# Earphone-6.net
KiCad netlist of a schematic drawn in Altium Designer
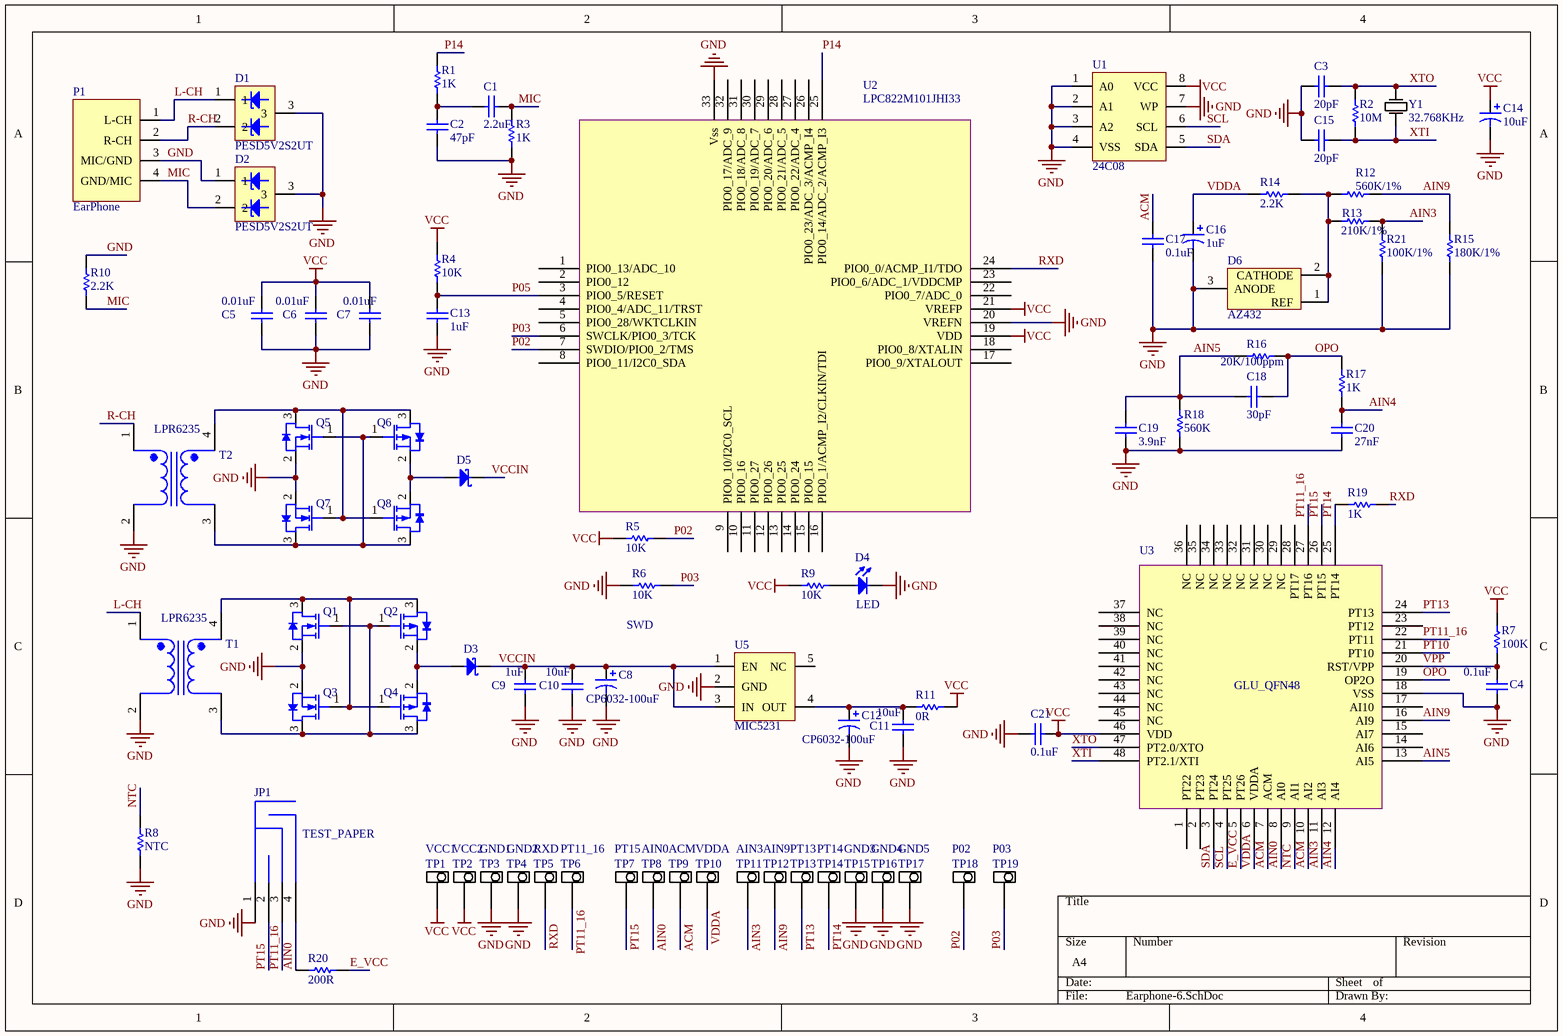
[diagram p0: Earphone-6.SchDoc]

(export (version "E")
  (design (tool "Eeschema 10.0.6"))
  (components
    (comp (ref "ACM") (value "TP9") (footprint "SIP1") (libsource (lib "Earphone") (part "TEST_PAD")))
    (comp (ref "AIN0") (value "TP8") (footprint "SIP1") (libsource (lib "Earphone") (part "TEST_PAD")))
    (comp (ref "AIN3") (value "TP11") (footprint "SIP1") (libsource (lib "Earphone") (part "TEST_PAD")))
    (comp (ref "AIN9") (value "TP12") (footprint "SIP1") (libsource (lib "Earphone") (part "TEST_PAD")))
    (comp (ref "C1") (value "2.2uF") (footprint "0402C") (libsource (lib "Schlib1") (part "CAP")))
    (comp (ref "C2") (value "47pF") (footprint "0402C") (libsource (lib "Schlib1") (part "CAP")))
    (comp (ref "C3") (value "20pF") (footprint "0402C") (libsource (lib "Earphone") (part "CAP")))
    (comp (ref "C4") (value "0.1uF") (footprint "0402C") (libsource (lib "Schlib1") (part "CAP")))
    (comp (ref "C5") (value "0.01uF") (footprint "0402C") (libsource (lib "Schlib1") (part "CAP")))
    (comp (ref "C6") (value "0.01uF") (footprint "0402C") (libsource (lib "Schlib1") (part "CAP")))
    (comp (ref "C7") (value "0.01uF") (footprint "0402C") (libsource (lib "Schlib1") (part "CAP")))
    (comp (ref "C8")
      (value "CP6032-100uF")
      (footprint "T3216-18[A]")
      (libsource (lib "Schlib1") (part "CAP POL2"))
    )
    (comp (ref "C9") (value "1uF") (footprint "0402C") (libsource (lib "Schlib1") (part "CAP")))
    (comp (ref "C10") (value "10uF") (footprint "0402C") (libsource (lib "Schlib1") (part "CAP")))
    (comp (ref "C11") (value "10uF") (footprint "0402C") (libsource (lib "Schlib1") (part "CAP")))
    (comp (ref "C12")
      (value "CP6032-100uF")
      (footprint "T3216-18[A]")
      (libsource (lib "Schlib1") (part "CAP POL2"))
    )
    (comp (ref "C13") (value "1uF") (footprint "0402C") (libsource (lib "Schlib1") (part "CAP")))
    (comp (ref "C14") (value "10uF") (footprint "0402C") (libsource (lib "Earphone") (part "CAP POL2")))
    (comp (ref "C15") (value "20pF") (footprint "0402C") (libsource (lib "Earphone") (part "CAP")))
    (comp (ref "C16") (value "1uF") (footprint "0402C") (libsource (lib "Earphone") (part "CAP POL2")))
    (comp (ref "C17") (value "0.1uF") (footprint "0402C") (libsource (lib "Earphone") (part "CAP")))
    (comp (ref "C18") (value "30pF") (footprint "0402C") (libsource (lib "Earphone") (part "CAP")))
    (comp (ref "C19") (value "3.9nF") (footprint "0402C") (libsource (lib "Earphone") (part "CAP")))
    (comp (ref "C20") (value "27nF") (footprint "0402C") (libsource (lib "Earphone") (part "CAP")))
    (comp (ref "C21") (value "0.1uF") (footprint "0402C") (libsource (lib "Earphone") (part "CAP")))
    (comp (ref "D1")
      (value "PESD5V2S2UT")
      (footprint "SOT23")
      (description "SOT23")
      (libsource (lib "Schlib1") (part "PESD5V2S2UT"))
    )
    (comp (ref "D2")
      (value "PESD5V2S2UT")
      (footprint "SOT23")
      (description "SOT23")
      (libsource (lib "Schlib1") (part "PESD5V2S2UT"))
    )
    (comp (ref "D3")
      (value "PMEG4002EJ")
      (footprint "SOD323")
      (description "SOD323F")
      (libsource (lib "Schlib1") (part "PMEG4002EJ"))
    )
    (comp (ref "D4") (value "LED") (footprint "0603L") (libsource (lib "Schlib1") (part "LED")))
    (comp (ref "D5")
      (value "PMEG4002EJ")
      (footprint "SOD323")
      (description "SOD323F")
      (libsource (lib "Schlib1") (part "PMEG4002EJ"))
    )
    (comp (ref "D6") (value "AZ432") (footprint "SOT23") (libsource (lib "Earphone") (part "AZ432")))
    (comp (ref "GND1") (value "TP3") (footprint "SIP1") (libsource (lib "Earphone") (part "TEST_PAD")))
    (comp (ref "GND2") (value "TP4") (footprint "SIP1") (libsource (lib "Earphone") (part "TEST_PAD")))
    (comp (ref "GND3") (value "TP15") (footprint "SIP1") (libsource (lib "Earphone") (part "TEST_PAD")))
    (comp (ref "GND4") (value "TP16") (footprint "SIP1") (libsource (lib "Earphone") (part "TEST_PAD")))
    (comp (ref "GND5") (value "TP17") (footprint "SIP1") (libsource (lib "Earphone") (part "TEST_PAD")))
    (comp (ref "JP1")
      (value "TEST_PAPER")
      (footprint "TEST_PAPER")
      (libsource (lib "Schlib1") (part "TEST_PAPER"))
    )
    (comp (ref "P1") (value "EarPhone") (footprint "USB-A") (libsource (lib "Schlib1") (part "EarPhone")))
    (comp (ref "P02") (value "TP18") (footprint "SIP1") (libsource (lib "Earphone") (part "TEST_PAD")))
    (comp (ref "P03") (value "TP19") (footprint "SIP1") (libsource (lib "Earphone") (part "TEST_PAD")))
    (comp (ref "PT11_16") (value "TP6") (footprint "SIP1") (libsource (lib "Earphone") (part "TEST_PAD")))
    (comp (ref "PT13") (value "TP13") (footprint "SIP1") (libsource (lib "Earphone") (part "TEST_PAD")))
    (comp (ref "PT14") (value "TP14") (footprint "SIP1") (libsource (lib "Earphone") (part "TEST_PAD")))
    (comp (ref "PT15") (value "TP7") (footprint "SIP1") (libsource (lib "Earphone") (part "TEST_PAD")))
    (comp (ref "Q1")
      (value "N-MOSFET")
      (footprint "SOT23")
      (description "4N80 N-Channel MOSFET")
      (libsource (lib "Schlib1") (part "N-MOSFET"))
    )
    (comp (ref "Q2")
      (value "P-MOSFET")
      (footprint "SOT23")
      (description "P-Channel MOSFET")
      (libsource (lib "Schlib1") (part "P-MOSFET"))
    )
    (comp (ref "Q3")
      (value "N-MOSFET")
      (footprint "SOT23")
      (description "4N80 N-Channel MOSFET")
      (libsource (lib "Schlib1") (part "N-MOSFET"))
    )
    (comp (ref "Q4")
      (value "P-MOSFET")
      (footprint "SOT23")
      (description "P-Channel MOSFET")
      (libsource (lib "") (part "P-MOSFET_1"))
    )
    (comp (ref "Q5")
      (value "N-MOSFET")
      (footprint "SOT23")
      (description "4N80 N-Channel MOSFET")
      (libsource (lib "Schlib1") (part "N-MOSFET"))
    )
    (comp (ref "Q6")
      (value "P-MOSFET")
      (footprint "SOT23")
      (description "P-Channel MOSFET")
      (libsource (lib "Schlib1") (part "P-MOSFET"))
    )
    (comp (ref "Q7")
      (value "N-MOSFET")
      (footprint "SOT23")
      (description "4N80 N-Channel MOSFET")
      (libsource (lib "Schlib1") (part "N-MOSFET"))
    )
    (comp (ref "Q8")
      (value "P-MOSFET")
      (footprint "SOT23")
      (description "P-Channel MOSFET")
      (libsource (lib "") (part "P-MOSFET_1"))
    )
    (comp (ref "R1") (value "1K") (footprint "0402R") (libsource (lib "Schlib1") (part "RES")))
    (comp (ref "R2") (value "10M") (footprint "0402R") (libsource (lib "Earphone") (part "RES")))
    (comp (ref "R3") (value "1K") (footprint "0402R") (libsource (lib "Schlib1") (part "RES")))
    (comp (ref "R4") (value "10K") (footprint "0402R") (libsource (lib "Schlib1") (part "RES")))
    (comp (ref "R5") (value "10K") (footprint "0402R") (libsource (lib "Schlib1") (part "RES")))
    (comp (ref "R6") (value "10K") (footprint "0402R") (libsource (lib "Schlib1") (part "RES")))
    (comp (ref "R7") (value "100K") (footprint "0402R") (libsource (lib "Schlib1") (part "RES")))
    (comp (ref "R8") (value "NTC") (footprint "0603R") (libsource (lib "Schlib1") (part "RES")))
    (comp (ref "R9") (value "10K") (footprint "0402R") (libsource (lib "Schlib1") (part "RES")))
    (comp (ref "R10") (value "2.2K") (footprint "0402R") (libsource (lib "Schlib1") (part "RES")))
    (comp (ref "R11") (value "0R") (footprint "0402R") (libsource (lib "Schlib1") (part "RES")))
    (comp (ref "R12") (value "560K/1%") (footprint "0402R") (libsource (lib "Earphone") (part "RES")))
    (comp (ref "R13") (value "210K/1%") (footprint "0402R") (libsource (lib "Earphone") (part "RES")))
    (comp (ref "R14") (value "2.2K") (footprint "0402R") (libsource (lib "Earphone") (part "RES")))
    (comp (ref "R15") (value "180K/1%") (footprint "0402R") (libsource (lib "Earphone") (part "RES")))
    (comp (ref "R16") (value "20K/100ppm") (footprint "0402R") (libsource (lib "Earphone") (part "RES")))
    (comp (ref "R17") (value "1K") (footprint "0402R") (libsource (lib "Earphone") (part "RES")))
    (comp (ref "R18") (value "560K") (footprint "0402R") (libsource (lib "Earphone") (part "RES")))
    (comp (ref "R19") (value "1K") (footprint "0402R") (libsource (lib "Earphone") (part "RES")))
    (comp (ref "R20") (value "200R") (footprint "0402R") (libsource (lib "Earphone") (part "RES")))
    (comp (ref "R21") (value "100K/1%") (footprint "0402R") (libsource (lib "Earphone") (part "RES")))
    (comp (ref "RXD") (value "TP5") (footprint "SIP1") (libsource (lib "Earphone") (part "TEST_PAD")))
    (comp (ref "T1") (value "LPR6235") (footprint "Trans EMI") (libsource (lib "Schlib1") (part "Trans EMI")))
    (comp (ref "T2") (value "LPR6235") (footprint "Trans EMI") (libsource (lib "Schlib1") (part "Trans EMI")))
    (comp (ref "U1") (value "24C08") (footprint "SOP-8") (libsource (lib "Earphone") (part "24C08")))
    (comp (ref "U2")
      (value "LPC822M101JHI33")
      (footprint "QFN50P500X500X100-33N")
      (libsource (lib "Schlib1") (part "LPC822M101JHI33"))
    )
    (comp (ref "U3")
      (value "GLU_QFN48")
      (footprint "QFN_48PIN")
      (libsource (lib "Earphone") (part "GLU_QFN48"))
    )
    (comp (ref "U5") (value "MIC5231") (footprint "SOT23-5") (libsource (lib "Schlib1") (part "MIC5231")))
    (comp (ref "VCC1") (value "TP1") (footprint "SIP1") (libsource (lib "Earphone") (part "TEST_PAD")))
    (comp (ref "VCC2") (value "TP2") (footprint "SIP1") (libsource (lib "Earphone") (part "TEST_PAD")))
    (comp (ref "VDDA") (value "TP10") (footprint "SIP1") (libsource (lib "Earphone") (part "TEST_PAD")))
    (comp (ref "Y1") (value "32.768KHz") (footprint "Y1") (libsource (lib "Earphone") (part "32.768KHz")))
  )
  (nets
    (net (code "1") (name "/ACM") (class "Default")
      (node (ref "ACM") (pin "1") (pintype "passive"))
      (node (ref "C17") (pin "2") (pinfunction "2_2") (pintype "passive"))
      (node (ref "U3") (pin "10") (pinfunction "AI2_10") (pintype "passive"))
      (node (ref "U3") (pin "7") (pinfunction "ACM_7") (pintype "passive"))
    )
    (net (code "2") (name "/AIN0") (class "Default")
      (node (ref "AIN0") (pin "1") (pintype "passive"))
      (node (ref "JP1") (pin "4") (pinfunction "P_4") (pintype "passive"))
      (node (ref "R20") (pin "1") (pinfunction "1_1") (pintype "passive"))
      (node (ref "U3") (pin "8") (pinfunction "AI0_8") (pintype "passive"))
    )
    (net (code "3") (name "/AIN3") (class "Default")
      (node (ref "AIN3") (pin "1") (pintype "passive"))
      (node (ref "R13") (pin "1") (pinfunction "1_1") (pintype "passive"))
      (node (ref "R21") (pin "2") (pinfunction "2_2") (pintype "passive"))
      (node (ref "U3") (pin "11") (pinfunction "AI3_11") (pintype "passive"))
    )
    (net (code "4") (name "/AIN4") (class "Default")
      (node (ref "C20") (pin "1") (pinfunction "1_1") (pintype "passive"))
      (node (ref "R17") (pin "1") (pinfunction "1_1") (pintype "passive"))
      (node (ref "U3") (pin "12") (pinfunction "AI4_12") (pintype "passive"))
    )
    (net (code "5") (name "/AIN5") (class "Default")
      (node (ref "C18") (pin "2") (pinfunction "2_2") (pintype "passive"))
      (node (ref "C19") (pin "2") (pinfunction "2_2") (pintype "passive"))
      (node (ref "R16") (pin "2") (pinfunction "2_2") (pintype "passive"))
      (node (ref "R18") (pin "1") (pinfunction "1_1") (pintype "passive"))
      (node (ref "U3") (pin "13") (pinfunction "AI5_13") (pintype "passive"))
    )
    (net (code "6") (name "/AIN9") (class "Default")
      (node (ref "AIN9") (pin "1") (pintype "passive"))
      (node (ref "R12") (pin "1") (pinfunction "1_1") (pintype "passive"))
      (node (ref "R15") (pin "1") (pinfunction "1_1") (pintype "passive"))
      (node (ref "U3") (pin "16") (pinfunction "AI9_16") (pintype "passive"))
    )
    (net (code "7") (name "/E_VCC") (class "Default")
      (node (ref "R20") (pin "2") (pinfunction "2_2") (pintype "passive"))
      (node (ref "U3") (pin "5") (pinfunction "PT26_5") (pintype "passive"))
    )
    (net (code "8") (name "/L-CH") (class "Default")
      (node (ref "D1") (pin "1") (pinfunction "1_1") (pintype "passive"))
      (node (ref "P1") (pin "1") (pinfunction "L-CH_1") (pintype "passive"))
      (node (ref "T1") (pin "1") (pinfunction "1_1") (pintype "passive"))
    )
    (net (code "9") (name "/MIC") (class "Default")
      (node (ref "C1") (pin "1") (pinfunction "1_1") (pintype "passive"))
      (node (ref "D2") (pin "2") (pinfunction "2_2") (pintype "passive"))
      (node (ref "P1") (pin "4") (pinfunction "GND/MIC_4") (pintype "passive"))
      (node (ref "R10") (pin "1") (pinfunction "1_1") (pintype "passive"))
      (node (ref "R3") (pin "1") (pinfunction "1_1") (pintype "passive"))
    )
    (net (code "10") (name "/NTC") (class "Default")
      (node (ref "R8") (pin "2") (pinfunction "2_2") (pintype "passive"))
      (node (ref "U3") (pin "9") (pinfunction "AI1_9") (pintype "passive"))
    )
    (net (code "11") (name "/OPO") (class "Default")
      (node (ref "C18") (pin "1") (pinfunction "1_1") (pintype "passive"))
      (node (ref "R16") (pin "1") (pinfunction "1_1") (pintype "passive"))
      (node (ref "R17") (pin "2") (pinfunction "2_2") (pintype "passive"))
      (node (ref "U3") (pin "19") (pinfunction "OP2O_19") (pintype "passive"))
    )
    (net (code "12") (name "/P02") (class "Default")
      (node (ref "P02") (pin "1") (pintype "passive"))
      (node (ref "R5") (pin "2") (pinfunction "2_2") (pintype "passive"))
      (node (ref "U2") (pin "7") (pinfunction "SWDIO/PIO0_2/TMS_7") (pintype "passive"))
    )
    (net (code "13") (name "/P03") (class "Default")
      (node (ref "P03") (pin "1") (pintype "passive"))
      (node (ref "R6") (pin "1") (pinfunction "1_1") (pintype "passive"))
      (node (ref "U2") (pin "6") (pinfunction "SWCLK/PIO0_3/TCK_6") (pintype "passive"))
    )
    (net (code "14") (name "/P05") (class "Default")
      (node (ref "C13") (pin "2") (pinfunction "2_2") (pintype "passive"))
      (node (ref "R4") (pin "1") (pinfunction "1_1") (pintype "passive"))
      (node (ref "U2") (pin "3") (pinfunction "PIO0_5/RESET_3") (pintype "passive"))
    )
    (net (code "15") (name "/P14") (class "Default")
      (node (ref "R1") (pin "1") (pinfunction "1_1") (pintype "passive"))
      (node (ref "U2") (pin "25") (pinfunction "PIO0_14/ADC_2/ACMP_I3_25") (pintype "passive"))
    )
    (net (code "16") (name "/PT10") (class "Default")
      (node (ref "U3") (pin "21") (pinfunction "PT10_21") (pintype "passive"))
    )
    (net (code "17") (name "/PT11_16") (class "Default")
      (node (ref "JP1") (pin "3") (pinfunction "NOP_3") (pintype "passive"))
      (node (ref "PT11_16") (pin "1") (pintype "passive"))
      (node (ref "U3") (pin "22") (pinfunction "PT11_22") (pintype "passive"))
      (node (ref "U3") (pin "27") (pinfunction "PT16_27") (pintype "passive"))
    )
    (net (code "18") (name "/PT13") (class "Default")
      (node (ref "PT13") (pin "1") (pintype "passive"))
      (node (ref "U3") (pin "24") (pinfunction "PT13_24") (pintype "passive"))
    )
    (net (code "19") (name "/PT14") (class "Default")
      (node (ref "PT14") (pin "1") (pintype "passive"))
      (node (ref "R19") (pin "2") (pinfunction "2_2") (pintype "passive"))
      (node (ref "U3") (pin "25") (pinfunction "PT14_25") (pintype "passive"))
    )
    (net (code "20") (name "/PT15") (class "Default")
      (node (ref "JP1") (pin "2") (pinfunction "PC10_2") (pintype "passive"))
      (node (ref "PT15") (pin "1") (pintype "passive"))
      (node (ref "U3") (pin "26") (pinfunction "PT15_26") (pintype "passive"))
    )
    (net (code "21") (name "/R-CH") (class "Default")
      (node (ref "D1") (pin "2") (pinfunction "2_2") (pintype "passive"))
      (node (ref "P1") (pin "2") (pinfunction "R-CH_2") (pintype "passive"))
      (node (ref "T2") (pin "1") (pinfunction "1_1") (pintype "passive"))
    )
    (net (code "22") (name "/RXD") (class "Default")
      (node (ref "R19") (pin "1") (pinfunction "1_1") (pintype "passive"))
      (node (ref "RXD") (pin "1") (pintype "passive"))
      (node (ref "U2") (pin "24") (pinfunction "PIO0_0/ACMP_I1/TDO_24") (pintype "passive"))
    )
    (net (code "23") (name "/SCL") (class "Default")
      (node (ref "U1") (pin "6") (pinfunction "SCL_6") (pintype "passive"))
      (node (ref "U3") (pin "4") (pinfunction "PT25_4") (pintype "passive"))
    )
    (net (code "24") (name "/SDA") (class "Default")
      (node (ref "U1") (pin "5") (pinfunction "SDA_5") (pintype "passive"))
      (node (ref "U3") (pin "3") (pinfunction "PT24_3") (pintype "passive"))
    )
    (net (code "25") (name "/VCCIN") (class "Default")
      (node (ref "C10") (pin "2") (pinfunction "2_2") (pintype "passive"))
      (node (ref "C8") (pin "1") (pinfunction "1_1") (pintype "passive"))
      (node (ref "C9") (pin "2") (pinfunction "2_2") (pintype "passive"))
      (node (ref "D3") (pin "1") (pinfunction "1_1") (pintype "passive"))
      (node (ref "D5") (pin "1") (pinfunction "1_1") (pintype "passive"))
      (node (ref "U5") (pin "1") (pinfunction "EN_1") (pintype "passive"))
      (node (ref "U5") (pin "3") (pinfunction "IN_3") (pintype "passive"))
    )
    (net (code "26") (name "/VDDA") (class "Default")
      (node (ref "C16") (pin "1") (pinfunction "1_1") (pintype "passive"))
      (node (ref "R14") (pin "1") (pinfunction "1_1") (pintype "passive"))
      (node (ref "U3") (pin "6") (pinfunction "VDDA_6") (pintype "passive"))
      (node (ref "VDDA") (pin "1") (pintype "passive"))
    )
    (net (code "27") (name "/VPP") (class "Default")
      (node (ref "C4") (pin "2") (pinfunction "2_2") (pintype "passive"))
      (node (ref "R7") (pin "1") (pinfunction "1_1") (pintype "passive"))
      (node (ref "U3") (pin "20") (pinfunction "RST/VPP_20") (pintype "passive"))
    )
    (net (code "28") (name "/XTI") (class "Default")
      (node (ref "C15") (pin "2") (pinfunction "2_2") (pintype "passive"))
      (node (ref "R2") (pin "1") (pinfunction "1_1") (pintype "passive"))
      (node (ref "U3") (pin "48") (pinfunction "PT2.1/XTI_48") (pintype "passive"))
      (node (ref "Y1") (pin "1") (pintype "passive"))
    )
    (net (code "29") (name "/XTO") (class "Default")
      (node (ref "C3") (pin "2") (pinfunction "2_2") (pintype "passive"))
      (node (ref "R2") (pin "2") (pinfunction "2_2") (pintype "passive"))
      (node (ref "U3") (pin "47") (pinfunction "PT2.0/XTO_47") (pintype "passive"))
      (node (ref "Y1") (pin "2") (pintype "passive"))
    )
    (net (code "30") (name "GND") (class "Default")
      (node (ref "C10") (pin "1") (pinfunction "1_1") (pintype "passive"))
      (node (ref "C11") (pin "1") (pinfunction "1_1") (pintype "passive"))
      (node (ref "C12") (pin "2") (pinfunction "2_2") (pintype "passive"))
      (node (ref "C13") (pin "1") (pinfunction "1_1") (pintype "passive"))
      (node (ref "C14") (pin "2") (pinfunction "2_2") (pintype "passive"))
      (node (ref "C15") (pin "1") (pinfunction "1_1") (pintype "passive"))
      (node (ref "C16") (pin "2") (pinfunction "2_2") (pintype "passive"))
      (node (ref "C17") (pin "1") (pinfunction "1_1") (pintype "passive"))
      (node (ref "C19") (pin "1") (pinfunction "1_1") (pintype "passive"))
      (node (ref "C2") (pin "1") (pinfunction "1_1") (pintype "passive"))
      (node (ref "C20") (pin "2") (pinfunction "2_2") (pintype "passive"))
      (node (ref "C21") (pin "1") (pinfunction "1_1") (pintype "passive"))
      (node (ref "C3") (pin "1") (pinfunction "1_1") (pintype "passive"))
      (node (ref "C4") (pin "1") (pinfunction "1_1") (pintype "passive"))
      (node (ref "C5") (pin "1") (pinfunction "1_1") (pintype "passive"))
      (node (ref "C6") (pin "1") (pinfunction "1_1") (pintype "passive"))
      (node (ref "C7") (pin "1") (pinfunction "1_1") (pintype "passive"))
      (node (ref "C8") (pin "2") (pinfunction "2_2") (pintype "passive"))
      (node (ref "C9") (pin "1") (pinfunction "1_1") (pintype "passive"))
      (node (ref "D1") (pin "3") (pinfunction "3_3") (pintype "passive"))
      (node (ref "D2") (pin "1") (pinfunction "1_1") (pintype "passive"))
      (node (ref "D2") (pin "3") (pinfunction "3_3") (pintype "passive"))
      (node (ref "D4") (pin "2") (pinfunction "K_2") (pintype "passive"))
      (node (ref "D6") (pin "3") (pinfunction "ANODE_3") (pintype "passive"))
      (node (ref "GND1") (pin "1") (pintype "passive"))
      (node (ref "GND2") (pin "1") (pintype "passive"))
      (node (ref "GND3") (pin "1") (pintype "passive"))
      (node (ref "GND4") (pin "1") (pintype "passive"))
      (node (ref "GND5") (pin "1") (pintype "passive"))
      (node (ref "JP1") (pin "1") (pinfunction "N_1") (pintype "passive"))
      (node (ref "P1") (pin "3") (pinfunction "MIC/GND_3") (pintype "passive"))
      (node (ref "Q1") (pin "2") (pinfunction "S_2") (pintype "passive"))
      (node (ref "Q3") (pin "2") (pinfunction "S_2") (pintype "passive"))
      (node (ref "Q5") (pin "2") (pinfunction "S_2") (pintype "passive"))
      (node (ref "Q7") (pin "2") (pinfunction "S_2") (pintype "passive"))
      (node (ref "R10") (pin "2") (pinfunction "2_2") (pintype "passive"))
      (node (ref "R15") (pin "2") (pinfunction "2_2") (pintype "passive"))
      (node (ref "R18") (pin "2") (pinfunction "2_2") (pintype "passive"))
      (node (ref "R21") (pin "1") (pinfunction "1_1") (pintype "passive"))
      (node (ref "R3") (pin "2") (pinfunction "2_2") (pintype "passive"))
      (node (ref "R6") (pin "2") (pinfunction "2_2") (pintype "passive"))
      (node (ref "R8") (pin "1") (pinfunction "1_1") (pintype "passive"))
      (node (ref "T1") (pin "2") (pinfunction "2_2") (pintype "passive"))
      (node (ref "T2") (pin "2") (pinfunction "2_2") (pintype "passive"))
      (node (ref "U1") (pin "1") (pinfunction "A0_1") (pintype "passive"))
      (node (ref "U1") (pin "2") (pinfunction "A1_2") (pintype "passive"))
      (node (ref "U1") (pin "3") (pinfunction "A2_3") (pintype "passive"))
      (node (ref "U1") (pin "4") (pinfunction "VSS_4") (pintype "passive"))
      (node (ref "U1") (pin "7") (pinfunction "WP_7") (pintype "passive"))
      (node (ref "U2") (pin "20") (pinfunction "VREFN_20") (pintype "passive"))
      (node (ref "U2") (pin "33") (pinfunction "Vss_33") (pintype "passive"))
      (node (ref "U3") (pin "18") (pinfunction "VSS_18") (pintype "passive"))
      (node (ref "U5") (pin "2") (pinfunction "GND_2") (pintype "passive"))
    )
    (net (code "31") (name "Net-(C1-Pad2)") (class "Default")
      (node (ref "C1") (pin "2") (pinfunction "2_2") (pintype "passive"))
      (node (ref "C2") (pin "2") (pinfunction "2_2") (pintype "passive"))
      (node (ref "R1") (pin "2") (pinfunction "2_2") (pintype "passive"))
    )
    (net (code "32") (name "Net-(D4-A)") (class "Default")
      (node (ref "D4") (pin "1") (pinfunction "A_1") (pintype "passive"))
      (node (ref "R9") (pin "2") (pinfunction "2_2") (pintype "passive"))
    )
    (net (code "33") (name "Net-(D6-CATHODE)") (class "Default")
      (node (ref "D6") (pin "1") (pinfunction "REF_1") (pintype "passive"))
      (node (ref "D6") (pin "2") (pinfunction "CATHODE_2") (pintype "passive"))
      (node (ref "R12") (pin "2") (pinfunction "2_2") (pintype "passive"))
      (node (ref "R13") (pin "2") (pinfunction "2_2") (pintype "passive"))
      (node (ref "R14") (pin "2") (pinfunction "2_2") (pintype "passive"))
    )
    (net (code "34") (name "Net-(Q1-D)") (class "Default")
      (node (ref "Q1") (pin "3") (pinfunction "D_3") (pintype "passive"))
      (node (ref "Q2") (pin "3") (pinfunction "D_3") (pintype "passive"))
      (node (ref "Q3") (pin "1") (pinfunction "G_1") (pintype "passive"))
      (node (ref "Q4") (pin "1") (pinfunction "G_1") (pintype "passive"))
      (node (ref "T1") (pin "4") (pinfunction "4_4") (pintype "passive"))
    )
    (net (code "35") (name "Net-(Q1-G)") (class "Default")
      (node (ref "Q1") (pin "1") (pinfunction "G_1") (pintype "passive"))
      (node (ref "Q2") (pin "1") (pinfunction "G_1") (pintype "passive"))
      (node (ref "Q3") (pin "3") (pinfunction "D_3") (pintype "passive"))
      (node (ref "Q4") (pin "3") (pinfunction "D_3") (pintype "passive"))
      (node (ref "T1") (pin "3") (pinfunction "3_3") (pintype "passive"))
    )
    (net (code "36") (name "Net-(Q2-S)") (class "Default")
      (node (ref "D3") (pin "2") (pinfunction "2_2") (pintype "passive"))
      (node (ref "Q2") (pin "2") (pinfunction "S_2") (pintype "passive"))
      (node (ref "Q4") (pin "2") (pinfunction "S_2") (pintype "passive"))
    )
    (net (code "37") (name "Net-(Q5-D)") (class "Default")
      (node (ref "Q5") (pin "3") (pinfunction "D_3") (pintype "passive"))
      (node (ref "Q6") (pin "3") (pinfunction "D_3") (pintype "passive"))
      (node (ref "Q7") (pin "1") (pinfunction "G_1") (pintype "passive"))
      (node (ref "Q8") (pin "1") (pinfunction "G_1") (pintype "passive"))
      (node (ref "T2") (pin "4") (pinfunction "4_4") (pintype "passive"))
    )
    (net (code "38") (name "Net-(Q5-G)") (class "Default")
      (node (ref "Q5") (pin "1") (pinfunction "G_1") (pintype "passive"))
      (node (ref "Q6") (pin "1") (pinfunction "G_1") (pintype "passive"))
      (node (ref "Q7") (pin "3") (pinfunction "D_3") (pintype "passive"))
      (node (ref "Q8") (pin "3") (pinfunction "D_3") (pintype "passive"))
      (node (ref "T2") (pin "3") (pinfunction "3_3") (pintype "passive"))
    )
    (net (code "39") (name "Net-(Q6-S)") (class "Default")
      (node (ref "D5") (pin "2") (pinfunction "2_2") (pintype "passive"))
      (node (ref "Q6") (pin "2") (pinfunction "S_2") (pintype "passive"))
      (node (ref "Q8") (pin "2") (pinfunction "S_2") (pintype "passive"))
    )
    (net (code "40") (name "Net-(U5-OUT)") (class "Default")
      (node (ref "C11") (pin "2") (pinfunction "2_2") (pintype "passive"))
      (node (ref "C12") (pin "1") (pinfunction "1_1") (pintype "passive"))
      (node (ref "R11") (pin "1") (pinfunction "1_1") (pintype "passive"))
      (node (ref "U5") (pin "4") (pinfunction "OUT_4") (pintype "passive"))
    )
    (net (code "41") (name "VCC") (class "Default")
      (node (ref "C14") (pin "1") (pinfunction "1_1") (pintype "passive"))
      (node (ref "C21") (pin "2") (pinfunction "2_2") (pintype "passive"))
      (node (ref "C5") (pin "2") (pinfunction "2_2") (pintype "passive"))
      (node (ref "C6") (pin "2") (pinfunction "2_2") (pintype "passive"))
      (node (ref "C7") (pin "2") (pinfunction "2_2") (pintype "passive"))
      (node (ref "R11") (pin "2") (pinfunction "2_2") (pintype "passive"))
      (node (ref "R4") (pin "2") (pinfunction "2_2") (pintype "passive"))
      (node (ref "R5") (pin "1") (pinfunction "1_1") (pintype "passive"))
      (node (ref "R7") (pin "2") (pinfunction "2_2") (pintype "passive"))
      (node (ref "R9") (pin "1") (pinfunction "1_1") (pintype "passive"))
      (node (ref "U1") (pin "8") (pinfunction "VCC_8") (pintype "passive"))
      (node (ref "U2") (pin "19") (pinfunction "VDD_19") (pintype "passive"))
      (node (ref "U2") (pin "21") (pinfunction "VREFP_21") (pintype "passive"))
      (node (ref "U3") (pin "46") (pinfunction "VDD_46") (pintype "passive"))
      (node (ref "VCC1") (pin "1") (pintype "passive"))
      (node (ref "VCC2") (pin "1") (pintype "passive"))
    )
    (net (code "42") (name "unconnected-(U2-PIO0_1{slash}ACMP_I2{slash}CLKIN{slash}TDI-Pad16)") (class "Default")
      (node (ref "U2") (pin "16") (pinfunction "PIO0_1/ACMP_I2/CLKIN/TDI_16") (pintype "passive"))
    )
    (net (code "43") (name "unconnected-(U2-PIO0_4{slash}ADC_11{slash}TRST-Pad4)") (class "Default")
      (node (ref "U2") (pin "4") (pinfunction "PIO0_4/ADC_11/TRST_4") (pintype "passive"))
    )
    (net (code "44") (name "unconnected-(U2-PIO0_6{slash}ADC_1{slash}VDDCMP-Pad23)") (class "Default")
      (node (ref "U2") (pin "23") (pinfunction "PIO0_6/ADC_1/VDDCMP_23") (pintype "passive"))
    )
    (net (code "45") (name "unconnected-(U2-PIO0_7{slash}ADC_0-Pad22)") (class "Default")
      (node (ref "U2") (pin "22") (pinfunction "PIO0_7/ADC_0_22") (pintype "passive"))
    )
    (net (code "46") (name "unconnected-(U2-PIO0_8{slash}XTALIN-Pad18)") (class "Default")
      (node (ref "U2") (pin "18") (pinfunction "PIO0_8/XTALIN_18") (pintype "passive"))
    )
    (net (code "47") (name "unconnected-(U2-PIO0_9{slash}XTALOUT-Pad17)") (class "Default")
      (node (ref "U2") (pin "17") (pinfunction "PIO0_9/XTALOUT_17") (pintype "passive"))
    )
    (net (code "48") (name "unconnected-(U2-PIO0_10{slash}I2C0_SCL-Pad9)") (class "Default")
      (node (ref "U2") (pin "9") (pinfunction "PIO0_10/I2C0_SCL_9") (pintype "passive"))
    )
    (net (code "49") (name "unconnected-(U2-PIO0_11{slash}I2C0_SDA-Pad8)") (class "Default")
      (node (ref "U2") (pin "8") (pinfunction "PIO0_11/I2C0_SDA_8") (pintype "passive"))
    )
    (net (code "50") (name "unconnected-(U2-PIO0_12-Pad2)") (class "Default")
      (node (ref "U2") (pin "2") (pinfunction "PIO0_12_2") (pintype "passive"))
    )
    (net (code "51") (name "unconnected-(U2-PIO0_13{slash}ADC_10-Pad1)") (class "Default")
      (node (ref "U2") (pin "1") (pinfunction "PIO0_13/ADC_10_1") (pintype "passive"))
    )
    (net (code "52") (name "unconnected-(U2-PIO0_15-Pad15)") (class "Default")
      (node (ref "U2") (pin "15") (pinfunction "PIO0_15_15") (pintype "passive"))
    )
    (net (code "53") (name "unconnected-(U2-PIO0_16-Pad10)") (class "Default")
      (node (ref "U2") (pin "10") (pinfunction "PIO0_16_10") (pintype "passive"))
    )
    (net (code "54") (name "unconnected-(U2-PIO0_17{slash}ADC_9-Pad32)") (class "Default")
      (node (ref "U2") (pin "32") (pinfunction "PIO0_17/ADC_9_32") (pintype "passive"))
    )
    (net (code "55") (name "unconnected-(U2-PIO0_18{slash}ADC_8-Pad31)") (class "Default")
      (node (ref "U2") (pin "31") (pinfunction "PIO0_18/ADC_8_31") (pintype "passive"))
    )
    (net (code "56") (name "unconnected-(U2-PIO0_19{slash}ADC_7-Pad30)") (class "Default")
      (node (ref "U2") (pin "30") (pinfunction "PIO0_19/ADC_7_30") (pintype "passive"))
    )
    (net (code "57") (name "unconnected-(U2-PIO0_20{slash}ADC_6-Pad29)") (class "Default")
      (node (ref "U2") (pin "29") (pinfunction "PIO0_20/ADC_6_29") (pintype "passive"))
    )
    (net (code "58") (name "unconnected-(U2-PIO0_21{slash}ADC_5-Pad28)") (class "Default")
      (node (ref "U2") (pin "28") (pinfunction "PIO0_21/ADC_5_28") (pintype "passive"))
    )
    (net (code "59") (name "unconnected-(U2-PIO0_22{slash}ADC_4-Pad27)") (class "Default")
      (node (ref "U2") (pin "27") (pinfunction "PIO0_22/ADC_4_27") (pintype "passive"))
    )
    (net (code "60") (name "unconnected-(U2-PIO0_23{slash}ADC_3{slash}ACMP_I4-Pad26)") (class "Default")
      (node (ref "U2") (pin "26") (pinfunction "PIO0_23/ADC_3/ACMP_I4_26") (pintype "passive"))
    )
    (net (code "61") (name "unconnected-(U2-PIO0_24-Pad14)") (class "Default")
      (node (ref "U2") (pin "14") (pinfunction "PIO0_24_14") (pintype "passive"))
    )
    (net (code "62") (name "unconnected-(U2-PIO0_25-Pad13)") (class "Default")
      (node (ref "U2") (pin "13") (pinfunction "PIO0_25_13") (pintype "passive"))
    )
    (net (code "63") (name "unconnected-(U2-PIO0_26-Pad12)") (class "Default")
      (node (ref "U2") (pin "12") (pinfunction "PIO0_26_12") (pintype "passive"))
    )
    (net (code "64") (name "unconnected-(U2-PIO0_27-Pad11)") (class "Default")
      (node (ref "U2") (pin "11") (pinfunction "PIO0_27_11") (pintype "passive"))
    )
    (net (code "65") (name "unconnected-(U2-PIO0_28{slash}WKTCLKIN-Pad5)") (class "Default")
      (node (ref "U2") (pin "5") (pinfunction "PIO0_28/WKTCLKIN_5") (pintype "passive"))
    )
    (net (code "66") (name "unconnected-(U3-AI6-Pad14)") (class "Default")
      (node (ref "U3") (pin "14") (pinfunction "AI6_14") (pintype "passive"))
    )
    (net (code "67") (name "unconnected-(U3-AI7-Pad15)") (class "Default")
      (node (ref "U3") (pin "15") (pinfunction "AI7_15") (pintype "passive"))
    )
    (net (code "68") (name "unconnected-(U3-AI10-Pad17)") (class "Default")
      (node (ref "U3") (pin "17") (pinfunction "AI10_17") (pintype "passive"))
    )
    (net (code "69") (name "unconnected-(U3-NC-Pad29)") (class "Default")
      (node (ref "U3") (pin "29") (pinfunction "NC_29") (pintype "passive"))
    )
    (net (code "70") (name "unconnected-(U3-NC-Pad30)") (class "Default")
      (node (ref "U3") (pin "30") (pinfunction "NC_30") (pintype "passive"))
    )
    (net (code "71") (name "unconnected-(U3-NC-Pad31)") (class "Default")
      (node (ref "U3") (pin "31") (pinfunction "NC_31") (pintype "passive"))
    )
    (net (code "72") (name "unconnected-(U3-NC-Pad32)") (class "Default")
      (node (ref "U3") (pin "32") (pinfunction "NC_32") (pintype "passive"))
    )
    (net (code "73") (name "unconnected-(U3-NC-Pad33)") (class "Default")
      (node (ref "U3") (pin "33") (pinfunction "NC_33") (pintype "passive"))
    )
    (net (code "74") (name "unconnected-(U3-NC-Pad34)") (class "Default")
      (node (ref "U3") (pin "34") (pinfunction "NC_34") (pintype "passive"))
    )
    (net (code "75") (name "unconnected-(U3-NC-Pad35)") (class "Default")
      (node (ref "U3") (pin "35") (pinfunction "NC_35") (pintype "passive"))
    )
    (net (code "76") (name "unconnected-(U3-NC-Pad36)") (class "Default")
      (node (ref "U3") (pin "36") (pinfunction "NC_36") (pintype "passive"))
    )
    (net (code "77") (name "unconnected-(U3-NC-Pad37)") (class "Default")
      (node (ref "U3") (pin "37") (pinfunction "NC_37") (pintype "passive"))
    )
    (net (code "78") (name "unconnected-(U3-NC-Pad38)") (class "Default")
      (node (ref "U3") (pin "38") (pinfunction "NC_38") (pintype "passive"))
    )
    (net (code "79") (name "unconnected-(U3-NC-Pad39)") (class "Default")
      (node (ref "U3") (pin "39") (pinfunction "NC_39") (pintype "passive"))
    )
    (net (code "80") (name "unconnected-(U3-NC-Pad40)") (class "Default")
      (node (ref "U3") (pin "40") (pinfunction "NC_40") (pintype "passive"))
    )
    (net (code "81") (name "unconnected-(U3-NC-Pad41)") (class "Default")
      (node (ref "U3") (pin "41") (pinfunction "NC_41") (pintype "passive"))
    )
    (net (code "82") (name "unconnected-(U3-NC-Pad42)") (class "Default")
      (node (ref "U3") (pin "42") (pinfunction "NC_42") (pintype "passive"))
    )
    (net (code "83") (name "unconnected-(U3-NC-Pad43)") (class "Default")
      (node (ref "U3") (pin "43") (pinfunction "NC_43") (pintype "passive"))
    )
    (net (code "84") (name "unconnected-(U3-NC-Pad44)") (class "Default")
      (node (ref "U3") (pin "44") (pinfunction "NC_44") (pintype "passive"))
    )
    (net (code "85") (name "unconnected-(U3-NC-Pad45)") (class "Default")
      (node (ref "U3") (pin "45") (pinfunction "NC_45") (pintype "passive"))
    )
    (net (code "86") (name "unconnected-(U3-PT12-Pad23)") (class "Default")
      (node (ref "U3") (pin "23") (pinfunction "PT12_23") (pintype "passive"))
    )
    (net (code "87") (name "unconnected-(U3-PT17-Pad28)") (class "Default")
      (node (ref "U3") (pin "28") (pinfunction "PT17_28") (pintype "passive"))
    )
    (net (code "88") (name "unconnected-(U3-PT22-Pad1)") (class "Default")
      (node (ref "U3") (pin "1") (pinfunction "PT22_1") (pintype "passive"))
    )
    (net (code "89") (name "unconnected-(U3-PT23-Pad2)") (class "Default")
      (node (ref "U3") (pin "2") (pinfunction "PT23_2") (pintype "passive"))
    )
    (net (code "90") (name "unconnected-(U5-NC-Pad5)") (class "Default")
      (node (ref "U5") (pin "5") (pinfunction "NC_5") (pintype "passive"))
    )
  )
)
